# 1-FOB.net
KiCad netlist of a schematic drawn in Altium Designer
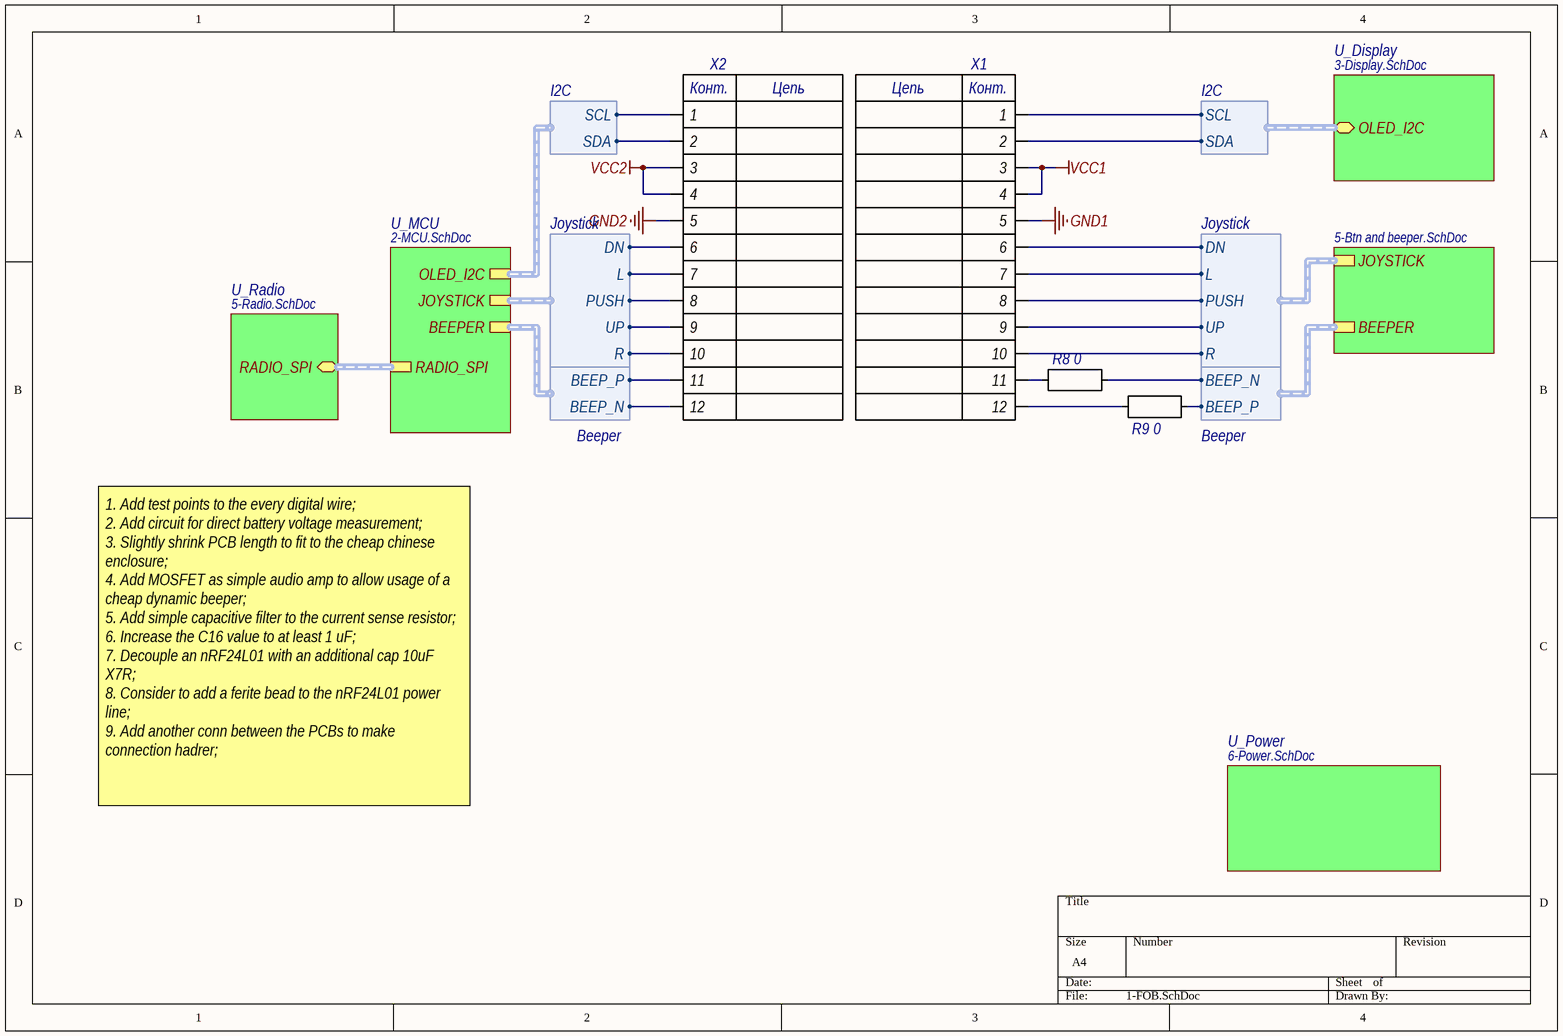
[diagram p0: 1-FOB.SchDoc]

(export (version "E")
  (design (tool "Eeschema 10.0.6"))
  (components
    (comp (ref "R8")
      (value "0")
      (footprint "CHIP_0402_R")
      (description "Резистор")
      (fields (field (name "PARTNUMBER") "RC0402JR-070RL") (field (name "MFG") "YAGEO"))
      (libsource (lib "RCL") (part "Резистор"))
    )
    (comp (ref "R9")
      (value "0")
      (footprint "CHIP_0402_R")
      (description "Резистор")
      (fields (field (name "PARTNUMBER") "RC0402JR-070RL") (field (name "MFG") "YAGEO"))
      (libsource (lib "RCL") (part "Резистор"))
    )
    (comp (ref "X1")
      (value "PLD-12")
      (footprint "PLD1.27-12 SMD")
      (fields (field (name "PARTNUMBER") "PLLD1.27-80 (2X40) SMD"))
      (libsource (lib "conn") (part "PLD-12"))
    )
    (comp (ref "X2")
      (value "PBD-12")
      (footprint "PBD1.27-12 SMD")
      (fields (field (name "PARTNUMBER") "PBD1.27-12 (2X06) SMD"))
      (libsource (lib "conn") (part "PBD-12"))
    )
  )
  (nets
    (net (code "8") (name "GND1") (class "Default")
      (node (ref "X1") (pin "5") (pinfunction "5_5") (pintype "passive"))
    )
    (net (code "9") (name "GND2") (class "Default")
      (node (ref "X2") (pin "5") (pinfunction "5_5") (pintype "passive"))
    )
    (net (code "10") (name "Net-(R8-Pad1)") (class "Default")
      (node (ref "R8") (pin "1") (pinfunction "1_1") (pintype "passive"))
      (node (ref "X1") (pin "11") (pinfunction "11_11") (pintype "passive"))
    )
    (net (code "11") (name "Net-(R9-Pad1)") (class "Default")
      (node (ref "R9") (pin "1") (pinfunction "1_1") (pintype "passive"))
      (node (ref "X1") (pin "12") (pinfunction "12_12") (pintype "passive"))
    )
    (net (code "12") (name "VCC1") (class "Default")
      (node (ref "X1") (pin "3") (pinfunction "3_3") (pintype "passive"))
      (node (ref "X1") (pin "4") (pinfunction "4_4") (pintype "passive"))
    )
    (net (code "13") (name "VCC2") (class "Default")
      (node (ref "X2") (pin "3") (pinfunction "3_3") (pintype "passive"))
      (node (ref "X2") (pin "4") (pinfunction "4_4") (pintype "passive"))
    )
    (net (code "14") (name "unconnected-(R8-Pad2)") (class "Default")
      (node (ref "R8") (pin "2") (pinfunction "2_2") (pintype "passive"))
    )
    (net (code "15") (name "unconnected-(R9-Pad2)") (class "Default")
      (node (ref "R9") (pin "2") (pinfunction "2_2") (pintype "passive"))
    )
    (net (code "16") (name "unconnected-(X1-Pad1)") (class "Default")
      (node (ref "X1") (pin "1") (pinfunction "1_1") (pintype "passive"))
    )
    (net (code "17") (name "unconnected-(X1-Pad2)") (class "Default")
      (node (ref "X1") (pin "2") (pinfunction "2_2") (pintype "passive"))
    )
    (net (code "18") (name "unconnected-(X1-Pad6)") (class "Default")
      (node (ref "X1") (pin "6") (pinfunction "6_6") (pintype "passive"))
    )
    (net (code "19") (name "unconnected-(X1-Pad7)") (class "Default")
      (node (ref "X1") (pin "7") (pinfunction "7_7") (pintype "passive"))
    )
    (net (code "20") (name "unconnected-(X1-Pad8)") (class "Default")
      (node (ref "X1") (pin "8") (pinfunction "8_8") (pintype "passive"))
    )
    (net (code "21") (name "unconnected-(X1-Pad9)") (class "Default")
      (node (ref "X1") (pin "9") (pinfunction "9_9") (pintype "passive"))
    )
    (net (code "22") (name "unconnected-(X1-Pad10)") (class "Default")
      (node (ref "X1") (pin "10") (pinfunction "10_10") (pintype "passive"))
    )
    (net (code "23") (name "unconnected-(X2-Pad1)") (class "Default")
      (node (ref "X2") (pin "1") (pinfunction "1_1") (pintype "passive"))
    )
    (net (code "24") (name "unconnected-(X2-Pad2)") (class "Default")
      (node (ref "X2") (pin "2") (pinfunction "2_2") (pintype "passive"))
    )
    (net (code "25") (name "unconnected-(X2-Pad6)") (class "Default")
      (node (ref "X2") (pin "6") (pinfunction "6_6") (pintype "passive"))
    )
    (net (code "26") (name "unconnected-(X2-Pad7)") (class "Default")
      (node (ref "X2") (pin "7") (pinfunction "7_7") (pintype "passive"))
    )
    (net (code "27") (name "unconnected-(X2-Pad8)") (class "Default")
      (node (ref "X2") (pin "8") (pinfunction "8_8") (pintype "passive"))
    )
    (net (code "28") (name "unconnected-(X2-Pad9)") (class "Default")
      (node (ref "X2") (pin "9") (pinfunction "9_9") (pintype "passive"))
    )
    (net (code "29") (name "unconnected-(X2-Pad10)") (class "Default")
      (node (ref "X2") (pin "10") (pinfunction "10_10") (pintype "passive"))
    )
    (net (code "30") (name "unconnected-(X2-Pad11)") (class "Default")
      (node (ref "X2") (pin "11") (pinfunction "11_11") (pintype "passive"))
    )
    (net (code "31") (name "unconnected-(X2-Pad12)") (class "Default")
      (node (ref "X2") (pin "12") (pinfunction "12_12") (pintype "passive"))
    )
  )
)
